# Noise_Generator.net
KiCad netlist of a schematic drawn in EAGLE
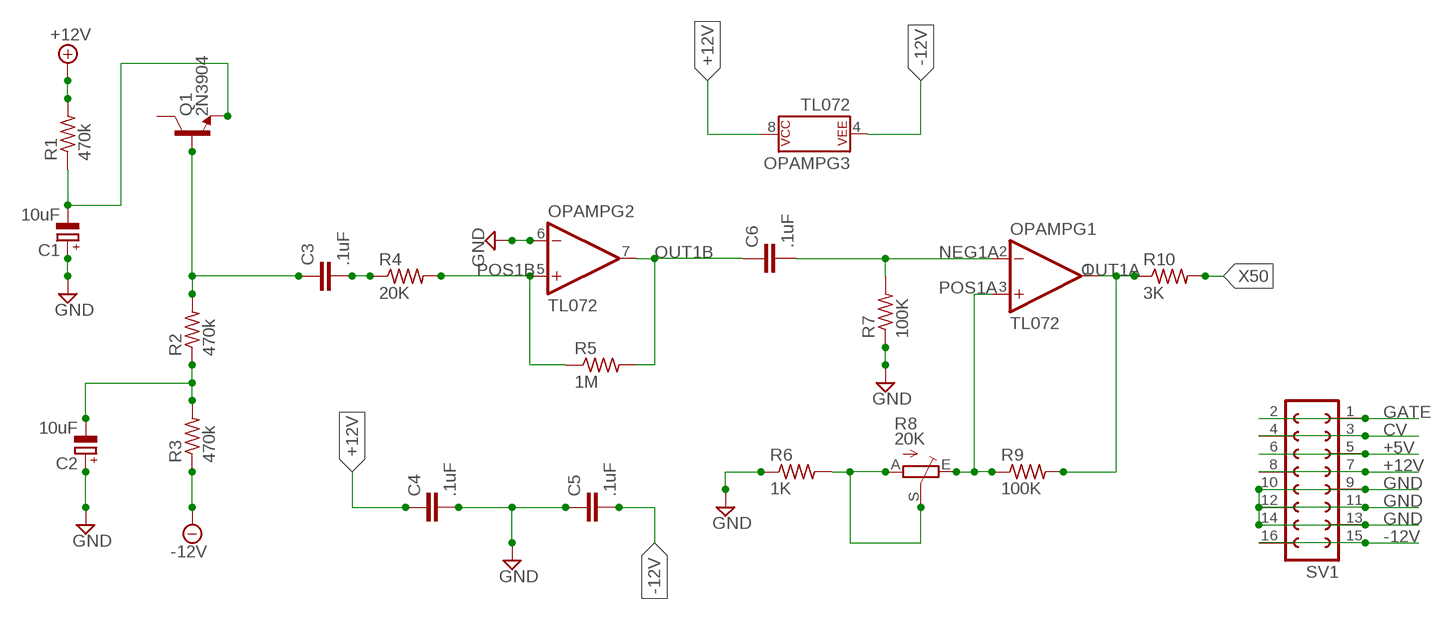
[diagram p0: schematic, sheet 1]

(export (version "E")
  (design (tool "Eeschema 10.0.6"))
  (components
    (comp (ref "C1")
      (value "10uF")
      (footprint "eagle-import:E2-4")
      (libsource (lib "eagle-import") (part "CPOL-EUE2-4"))
    )
    (comp (ref "C2")
      (value "10uF")
      (footprint "eagle-import:E2-4")
      (libsource (lib "eagle-import") (part "CPOL-EUE2-4"))
    )
    (comp (ref "C3")
      (value ".1uF")
      (footprint "eagle-import:C025-024X044")
      (libsource (lib "eagle-import") (part "C-EU025-024X044"))
    )
    (comp (ref "C4")
      (value ".1uF")
      (footprint "eagle-import:C025-024X044")
      (libsource (lib "eagle-import") (part "C-EU025-024X044"))
    )
    (comp (ref "C5")
      (value ".1uF")
      (footprint "eagle-import:C025-024X044")
      (libsource (lib "eagle-import") (part "C-EU025-024X044"))
    )
    (comp (ref "C6")
      (value ".1uF")
      (footprint "eagle-import:C025-024X044")
      (libsource (lib "eagle-import") (part "C-EU025-024X044"))
    )
    (comp (ref "OPAMP")
      (value "TL072")
      (footprint "eagle-import:SO08")
      (libsource (lib "eagle-import") (part "OPAMP-DUALU"))
    )
    (comp (ref "Q1")
      (value "2N3904")
      (footprint "eagle-import:TO-92")
      (libsource (lib "eagle-import") (part "TRANS_NPN-2N3904"))
    )
    (comp (ref "R1")
      (value "470k")
      (footprint "eagle-import:0309_12")
      (libsource (lib "eagle-import") (part "R-US_0309/12"))
    )
    (comp (ref "R2")
      (value "470k")
      (footprint "eagle-import:0309_12")
      (libsource (lib "eagle-import") (part "R-US_0309/12"))
    )
    (comp (ref "R3")
      (value "470k")
      (footprint "eagle-import:0309_12")
      (libsource (lib "eagle-import") (part "R-US_0309/12"))
    )
    (comp (ref "R4")
      (value "20K")
      (footprint "eagle-import:0309_12")
      (libsource (lib "eagle-import") (part "R-US_0309/12"))
    )
    (comp (ref "R5")
      (value "1M")
      (footprint "eagle-import:0309_12")
      (libsource (lib "eagle-import") (part "R-US_0309/12"))
    )
    (comp (ref "R6")
      (value "1K")
      (footprint "eagle-import:0309_12")
      (libsource (lib "eagle-import") (part "R-US_0309/12"))
    )
    (comp (ref "R7")
      (value "100K")
      (footprint "eagle-import:0309_12")
      (libsource (lib "eagle-import") (part "R-US_0309/12"))
    )
    (comp (ref "R8")
      (value "20K")
      (footprint "eagle-import:RJ9W")
      (libsource (lib "eagle-import") (part "TRIM_EU-RJ9W"))
    )
    (comp (ref "R9")
      (value "100K")
      (footprint "eagle-import:0309_12")
      (libsource (lib "eagle-import") (part "R-US_0309/12"))
    )
    (comp (ref "R10")
      (value "3K")
      (footprint "eagle-import:0309_12")
      (libsource (lib "eagle-import") (part "R-US_0309/12"))
    )
    (comp (ref "SV1")
      (value "FE08-2")
      (footprint "eagle-import:FE08-2")
      (libsource (lib "eagle-import") (part "FE08-2"))
    )
  )
  (nets
    (net (code "1") (name "+12V") (class "Default")
      (node (ref "C4") (pin "1") (pinfunction "1_1") (pintype "passive"))
      (node (ref "OPAMP") (pin "8") (pinfunction "P$V+_8") (pintype "bidirectional"))
      (node (ref "R1") (pin "2") (pinfunction "2_2") (pintype "passive"))
      (node (ref "SV1") (pin "7") (pinfunction "7_7") (pintype "passive"))
      (node (ref "SV1") (pin "8") (pinfunction "8_8") (pintype "passive"))
    )
    (net (code "2") (name "-12V") (class "Default")
      (node (ref "C5") (pin "2") (pinfunction "2_2") (pintype "passive"))
      (node (ref "OPAMP") (pin "4") (pinfunction "P$V-_4") (pintype "bidirectional"))
      (node (ref "R3") (pin "1") (pinfunction "1_1") (pintype "passive"))
      (node (ref "SV1") (pin "15") (pinfunction "15_15") (pintype "passive"))
      (node (ref "SV1") (pin "16") (pinfunction "16_16") (pintype "passive"))
    )
    (net (code "3") (name "/+5V") (class "Default")
      (node (ref "SV1") (pin "5") (pinfunction "5_5") (pintype "passive"))
      (node (ref "SV1") (pin "6") (pinfunction "6_6") (pintype "passive"))
    )
    (net (code "4") (name "/CV") (class "Default")
      (node (ref "SV1") (pin "3") (pinfunction "3_3") (pintype "passive"))
      (node (ref "SV1") (pin "4") (pinfunction "4_4") (pintype "passive"))
    )
    (net (code "5") (name "/GATE") (class "Default")
      (node (ref "SV1") (pin "1") (pinfunction "1_1") (pintype "passive"))
      (node (ref "SV1") (pin "2") (pinfunction "2_2") (pintype "passive"))
    )
    (net (code "6") (name "/NEG1A") (class "Default")
      (node (ref "C6") (pin "2") (pinfunction "2_2") (pintype "passive"))
      (node (ref "OPAMP") (pin "2") (pinfunction "-IN_2") (pintype "input"))
      (node (ref "R7") (pin "2") (pinfunction "2_2") (pintype "passive"))
    )
    (net (code "7") (name "/OUT1A") (class "Default")
      (node (ref "OPAMP") (pin "1") (pinfunction "OUT_1") (pintype "output"))
      (node (ref "R10") (pin "1") (pinfunction "1_1") (pintype "passive"))
      (node (ref "R9") (pin "2") (pinfunction "2_2") (pintype "passive"))
    )
    (net (code "8") (name "/OUT1B") (class "Default")
      (node (ref "C6") (pin "1") (pinfunction "1_1") (pintype "passive"))
      (node (ref "OPAMP") (pin "7") (pinfunction "OUT_7") (pintype "output"))
      (node (ref "R5") (pin "2") (pinfunction "2_2") (pintype "passive"))
    )
    (net (code "9") (name "/POS1A") (class "Default")
      (node (ref "OPAMP") (pin "3") (pinfunction "+IN_3") (pintype "input"))
      (node (ref "R8") (pin "E") (pinfunction "E_E") (pintype "passive"))
      (node (ref "R9") (pin "1") (pinfunction "1_1") (pintype "passive"))
    )
    (net (code "10") (name "/POS1B") (class "Default")
      (node (ref "OPAMP") (pin "5") (pinfunction "+IN_5") (pintype "input"))
      (node (ref "R4") (pin "2") (pinfunction "2_2") (pintype "passive"))
      (node (ref "R5") (pin "1") (pinfunction "1_1") (pintype "passive"))
    )
    (net (code "11") (name "GND") (class "Default")
      (node (ref "C1") (pin "+") (pinfunction "+_+") (pintype "passive"))
      (node (ref "C2") (pin "+") (pinfunction "+_+") (pintype "passive"))
      (node (ref "C4") (pin "2") (pinfunction "2_2") (pintype "passive"))
      (node (ref "C5") (pin "1") (pinfunction "1_1") (pintype "passive"))
      (node (ref "OPAMP") (pin "6") (pinfunction "-IN_6") (pintype "input"))
      (node (ref "R6") (pin "1") (pinfunction "1_1") (pintype "passive"))
      (node (ref "R7") (pin "1") (pinfunction "1_1") (pintype "passive"))
      (node (ref "SV1") (pin "10") (pinfunction "10_10") (pintype "passive"))
      (node (ref "SV1") (pin "11") (pinfunction "11_11") (pintype "passive"))
      (node (ref "SV1") (pin "12") (pinfunction "12_12") (pintype "passive"))
      (node (ref "SV1") (pin "13") (pinfunction "13_13") (pintype "passive"))
      (node (ref "SV1") (pin "14") (pinfunction "14_14") (pintype "passive"))
      (node (ref "SV1") (pin "9") (pinfunction "9_9") (pintype "passive"))
    )
    (net (code "12") (name "Net-(C2-Pad-)") (class "Default")
      (node (ref "C2") (pin "-") (pinfunction "-_-") (pintype "passive"))
      (node (ref "R2") (pin "1") (pinfunction "1_1") (pintype "passive"))
      (node (ref "R3") (pin "2") (pinfunction "2_2") (pintype "passive"))
    )
    (net (code "13") (name "Net-(C3-Pad2)") (class "Default")
      (node (ref "C3") (pin "2") (pinfunction "2_2") (pintype "passive"))
      (node (ref "R4") (pin "1") (pinfunction "1_1") (pintype "passive"))
    )
    (net (code "14") (name "Net-(Q1-B)") (class "Default")
      (node (ref "C3") (pin "1") (pinfunction "1_1") (pintype "passive"))
      (node (ref "Q1") (pin "2") (pinfunction "B_2") (pintype "passive"))
      (node (ref "R2") (pin "2") (pinfunction "2_2") (pintype "passive"))
    )
    (net (code "15") (name "Net-(Q1-E)") (class "Default")
      (node (ref "C1") (pin "-") (pinfunction "-_-") (pintype "passive"))
      (node (ref "Q1") (pin "1") (pinfunction "E_1") (pintype "passive"))
      (node (ref "R1") (pin "1") (pinfunction "1_1") (pintype "passive"))
    )
    (net (code "16") (name "Net-(R6-Pad2)") (class "Default")
      (node (ref "R6") (pin "2") (pinfunction "2_2") (pintype "passive"))
      (node (ref "R8") (pin "A") (pinfunction "A_A") (pintype "passive"))
      (node (ref "R8") (pin "S") (pinfunction "S_S") (pintype "passive"))
    )
    (net (code "17") (name "X50") (class "Default")
      (node (ref "R10") (pin "2") (pinfunction "2_2") (pintype "passive"))
    )
    (net (code "18") (name "unconnected-(Q1-C-Pad3)") (class "Default")
      (node (ref "Q1") (pin "3") (pinfunction "C_3") (pintype "passive"))
    )
  )
)
